# Tetris.net
KiCad netlist of a schematic drawn in Altium Designer
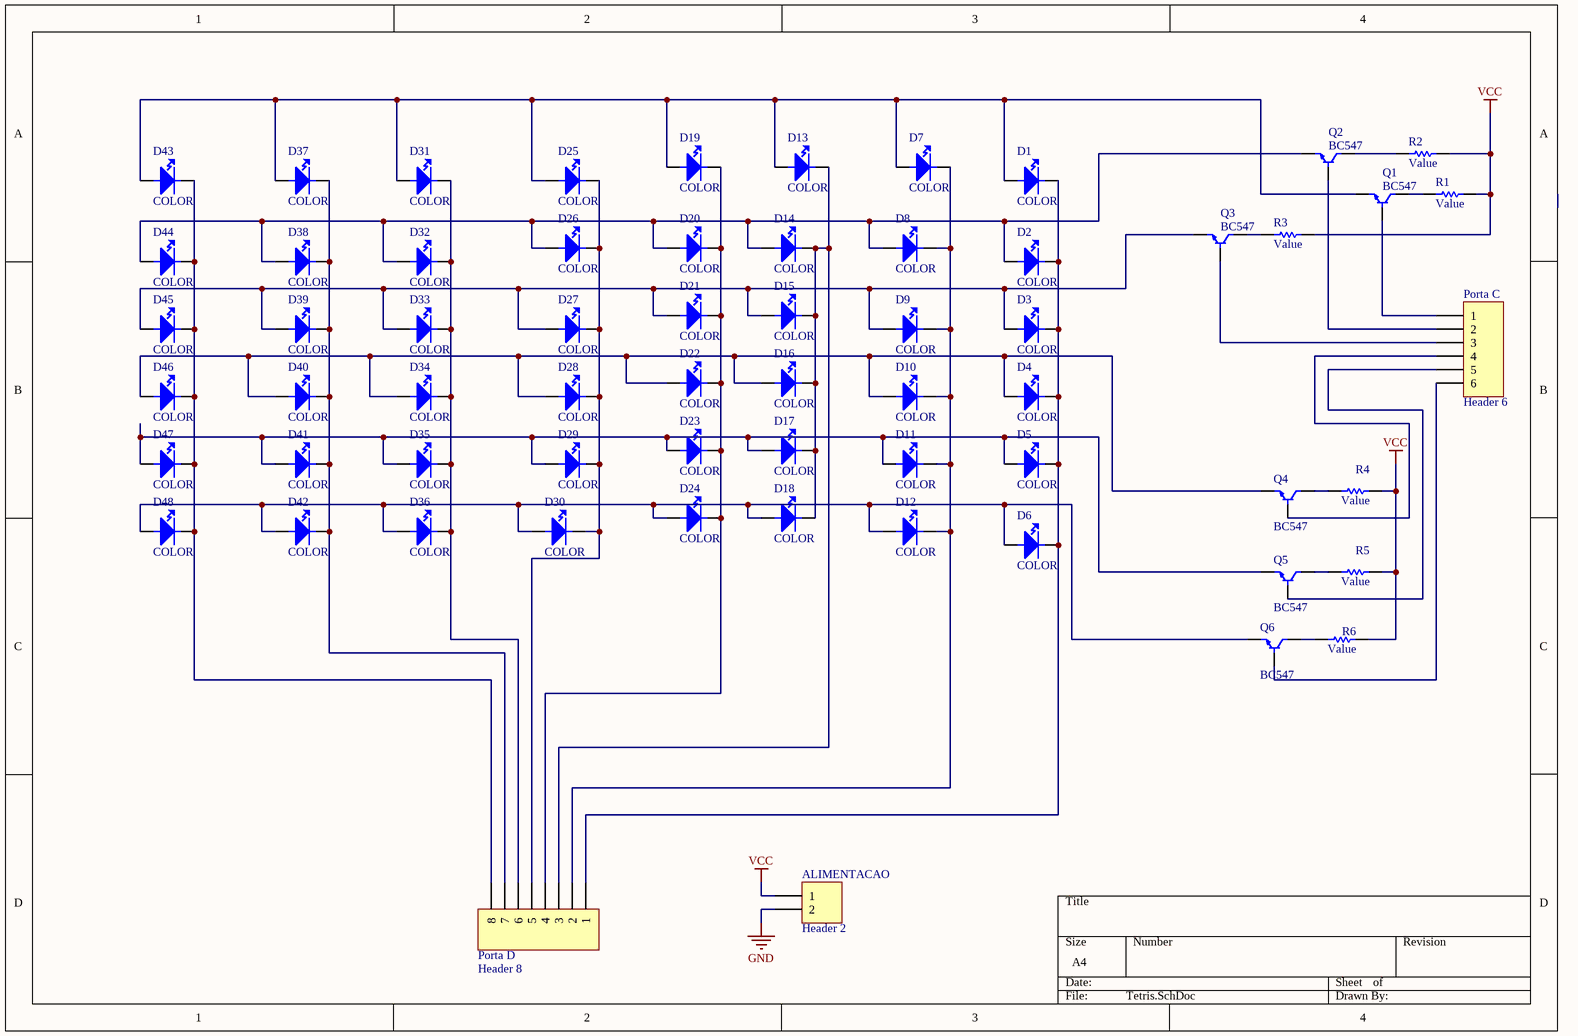
[diagram p0: Tetris.SchDoc]

(export (version "E")
  (design (tool "Eeschema 10.0.6"))
  (components
    (comp (ref "ALIMENTACAO")
      (value "Header 2")
      (footprint "HDR1X2")
      (description "Header, 2-Pin")
      (fields (field (name "PUBLISHER") "Altium Limited"))
      (libsource (lib "R2R - Nova") (part "Header 2"))
    )
    (comp (ref "D1")
      (value "COLOR")
      (footprint "TO1-5mm-Yellow")
      (description "Light Emitting Diode")
      (libsource (lib "R2R") (part "LED"))
    )
    (comp (ref "D2")
      (value "COLOR")
      (footprint "TO1-5mm-Yellow")
      (description "Light Emitting Diode")
      (libsource (lib "R2R") (part "LED"))
    )
    (comp (ref "D3")
      (value "COLOR")
      (footprint "TO1-5mm-Yellow")
      (description "Light Emitting Diode")
      (libsource (lib "R2R") (part "LED"))
    )
    (comp (ref "D4")
      (value "COLOR")
      (footprint "TO1-5mm-Yellow")
      (description "Light Emitting Diode")
      (libsource (lib "R2R") (part "LED"))
    )
    (comp (ref "D5")
      (value "COLOR")
      (footprint "TO1-5mm-Yellow")
      (description "Light Emitting Diode")
      (libsource (lib "R2R") (part "LED"))
    )
    (comp (ref "D6")
      (value "COLOR")
      (footprint "TO1-5mm-Yellow")
      (description "Light Emitting Diode")
      (libsource (lib "R2R") (part "LED"))
    )
    (comp (ref "D7")
      (value "COLOR")
      (footprint "TO1-5mm-Yellow")
      (description "Light Emitting Diode")
      (libsource (lib "R2R") (part "LED"))
    )
    (comp (ref "D8")
      (value "COLOR")
      (footprint "TO1-5mm-Yellow")
      (description "Light Emitting Diode")
      (libsource (lib "R2R") (part "LED"))
    )
    (comp (ref "D9")
      (value "COLOR")
      (footprint "TO1-5mm-Yellow")
      (description "Light Emitting Diode")
      (libsource (lib "R2R") (part "LED"))
    )
    (comp (ref "D10")
      (value "COLOR")
      (footprint "TO1-5mm-Yellow")
      (description "Light Emitting Diode")
      (libsource (lib "R2R") (part "LED"))
    )
    (comp (ref "D11")
      (value "COLOR")
      (footprint "TO1-5mm-Yellow")
      (description "Light Emitting Diode")
      (libsource (lib "R2R") (part "LED"))
    )
    (comp (ref "D12")
      (value "COLOR")
      (footprint "TO1-5mm-Yellow")
      (description "Light Emitting Diode")
      (libsource (lib "R2R") (part "LED"))
    )
    (comp (ref "D13")
      (value "COLOR")
      (footprint "TO1-5mm-Yellow")
      (description "Light Emitting Diode")
      (libsource (lib "R2R") (part "LED"))
    )
    (comp (ref "D14")
      (value "COLOR")
      (footprint "TO1-5mm-Yellow")
      (description "Light Emitting Diode")
      (libsource (lib "R2R") (part "LED"))
    )
    (comp (ref "D15")
      (value "COLOR")
      (footprint "TO1-5mm-Yellow")
      (description "Light Emitting Diode")
      (libsource (lib "R2R") (part "LED"))
    )
    (comp (ref "D16")
      (value "COLOR")
      (footprint "TO1-5mm-Yellow")
      (description "Light Emitting Diode")
      (libsource (lib "R2R") (part "LED"))
    )
    (comp (ref "D17")
      (value "COLOR")
      (footprint "TO1-5mm-Yellow")
      (description "Light Emitting Diode")
      (libsource (lib "R2R") (part "LED"))
    )
    (comp (ref "D18")
      (value "COLOR")
      (footprint "TO1-5mm-Yellow")
      (description "Light Emitting Diode")
      (libsource (lib "R2R") (part "LED"))
    )
    (comp (ref "D19")
      (value "COLOR")
      (footprint "TO1-5mm-Yellow")
      (description "Light Emitting Diode")
      (libsource (lib "R2R") (part "LED"))
    )
    (comp (ref "D20")
      (value "COLOR")
      (footprint "TO1-5mm-Yellow")
      (description "Light Emitting Diode")
      (libsource (lib "R2R") (part "LED"))
    )
    (comp (ref "D21")
      (value "COLOR")
      (footprint "TO1-5mm-Yellow")
      (description "Light Emitting Diode")
      (libsource (lib "R2R") (part "LED"))
    )
    (comp (ref "D22")
      (value "COLOR")
      (footprint "TO1-5mm-Yellow")
      (description "Light Emitting Diode")
      (libsource (lib "R2R") (part "LED"))
    )
    (comp (ref "D23")
      (value "COLOR")
      (footprint "TO1-5mm-Yellow")
      (description "Light Emitting Diode")
      (libsource (lib "R2R") (part "LED"))
    )
    (comp (ref "D24")
      (value "COLOR")
      (footprint "TO1-5mm-Yellow")
      (description "Light Emitting Diode")
      (libsource (lib "R2R") (part "LED"))
    )
    (comp (ref "D25")
      (value "COLOR")
      (footprint "TO1-5mm-Yellow")
      (description "Light Emitting Diode")
      (libsource (lib "R2R") (part "LED"))
    )
    (comp (ref "D26")
      (value "COLOR")
      (footprint "TO1-5mm-Yellow")
      (description "Light Emitting Diode")
      (libsource (lib "R2R") (part "LED"))
    )
    (comp (ref "D27")
      (value "COLOR")
      (footprint "TO1-5mm-Yellow")
      (description "Light Emitting Diode")
      (libsource (lib "R2R") (part "LED"))
    )
    (comp (ref "D28")
      (value "COLOR")
      (footprint "TO1-5mm-Yellow")
      (description "Light Emitting Diode")
      (libsource (lib "R2R") (part "LED"))
    )
    (comp (ref "D29")
      (value "COLOR")
      (footprint "TO1-5mm-Yellow")
      (description "Light Emitting Diode")
      (libsource (lib "R2R") (part "LED"))
    )
    (comp (ref "D30")
      (value "COLOR")
      (footprint "TO1-5mm-Yellow")
      (description "Light Emitting Diode")
      (libsource (lib "R2R") (part "LED"))
    )
    (comp (ref "D31")
      (value "COLOR")
      (footprint "TO1-5mm-Yellow")
      (description "Light Emitting Diode")
      (libsource (lib "R2R") (part "LED"))
    )
    (comp (ref "D32")
      (value "COLOR")
      (footprint "TO1-5mm-Yellow")
      (description "Light Emitting Diode")
      (libsource (lib "R2R") (part "LED"))
    )
    (comp (ref "D33")
      (value "COLOR")
      (footprint "TO1-5mm-Yellow")
      (description "Light Emitting Diode")
      (libsource (lib "R2R") (part "LED"))
    )
    (comp (ref "D34")
      (value "COLOR")
      (footprint "TO1-5mm-Yellow")
      (description "Light Emitting Diode")
      (libsource (lib "R2R") (part "LED"))
    )
    (comp (ref "D35")
      (value "COLOR")
      (footprint "TO1-5mm-Yellow")
      (description "Light Emitting Diode")
      (libsource (lib "R2R") (part "LED"))
    )
    (comp (ref "D36")
      (value "COLOR")
      (footprint "TO1-5mm-Yellow")
      (description "Light Emitting Diode")
      (libsource (lib "R2R") (part "LED"))
    )
    (comp (ref "D37")
      (value "COLOR")
      (footprint "TO1-5mm-Yellow")
      (description "Light Emitting Diode")
      (libsource (lib "R2R") (part "LED"))
    )
    (comp (ref "D38")
      (value "COLOR")
      (footprint "TO1-5mm-Yellow")
      (description "Light Emitting Diode")
      (libsource (lib "R2R") (part "LED"))
    )
    (comp (ref "D39")
      (value "COLOR")
      (footprint "TO1-5mm-Yellow")
      (description "Light Emitting Diode")
      (libsource (lib "R2R") (part "LED"))
    )
    (comp (ref "D40")
      (value "COLOR")
      (footprint "TO1-5mm-Yellow")
      (description "Light Emitting Diode")
      (libsource (lib "R2R") (part "LED"))
    )
    (comp (ref "D41")
      (value "COLOR")
      (footprint "TO1-5mm-Yellow")
      (description "Light Emitting Diode")
      (libsource (lib "R2R") (part "LED"))
    )
    (comp (ref "D42")
      (value "COLOR")
      (footprint "TO1-5mm-Yellow")
      (description "Light Emitting Diode")
      (libsource (lib "R2R") (part "LED"))
    )
    (comp (ref "D43")
      (value "COLOR")
      (footprint "TO1-5mm-Yellow")
      (description "Light Emitting Diode")
      (libsource (lib "R2R") (part "LED"))
    )
    (comp (ref "D44")
      (value "COLOR")
      (footprint "TO1-5mm-Yellow")
      (description "Light Emitting Diode")
      (libsource (lib "R2R") (part "LED"))
    )
    (comp (ref "D45")
      (value "COLOR")
      (footprint "TO1-5mm-Yellow")
      (description "Light Emitting Diode")
      (libsource (lib "R2R") (part "LED"))
    )
    (comp (ref "D46")
      (value "COLOR")
      (footprint "TO1-5mm-Yellow")
      (description "Light Emitting Diode")
      (libsource (lib "R2R") (part "LED"))
    )
    (comp (ref "D47")
      (value "COLOR")
      (footprint "TO1-5mm-Yellow")
      (description "Light Emitting Diode")
      (libsource (lib "R2R") (part "LED"))
    )
    (comp (ref "D48")
      (value "COLOR")
      (footprint "TO1-5mm-Yellow")
      (description "Light Emitting Diode")
      (libsource (lib "R2R") (part "LED"))
    )
    (comp (ref "Porta C")
      (value "Header 6")
      (footprint "HDR1X6")
      (description "Header, 6-Pin")
      (fields (field (name "PUBLISHER") "Altium Limited"))
      (libsource (lib "R2R - Nova") (part "Header 6"))
    )
    (comp (ref "Porta D")
      (value "Header 8")
      (footprint "HDR1X8")
      (description "Header, 8-Pin")
      (fields (field (name "PUBLISHER") "Altium Limited"))
      (libsource (lib "R2R - Nova") (part "Header 8"))
    )
    (comp (ref "Q1")
      (value "BC547")
      (footprint "TO-92/CBE")
      (description "NPN Epitaxial Silicon Transistor")
      (fields (field (name "COMPLEMENTARY PART") "BC557"))
      (libsource (lib "GPDSE") (part "BC547"))
    )
    (comp (ref "Q2")
      (value "BC547")
      (footprint "TO-92/CBE")
      (description "NPN Epitaxial Silicon Transistor")
      (fields (field (name "COMPLEMENTARY PART") "BC557"))
      (libsource (lib "GPDSE") (part "BC547"))
    )
    (comp (ref "Q3")
      (value "BC547")
      (footprint "TO-92/CBE")
      (description "NPN Epitaxial Silicon Transistor")
      (fields (field (name "COMPLEMENTARY PART") "BC557"))
      (libsource (lib "GPDSE") (part "BC547"))
    )
    (comp (ref "Q4")
      (value "BC547")
      (footprint "TO-92/CBE")
      (description "NPN Epitaxial Silicon Transistor")
      (fields (field (name "COMPLEMENTARY PART") "BC557"))
      (libsource (lib "GPDSE") (part "BC547"))
    )
    (comp (ref "Q5")
      (value "BC547")
      (footprint "TO-92/CBE")
      (description "NPN Epitaxial Silicon Transistor")
      (fields (field (name "COMPLEMENTARY PART") "BC557"))
      (libsource (lib "GPDSE") (part "BC547"))
    )
    (comp (ref "Q6")
      (value "BC547")
      (footprint "TO-92/CBE")
      (description "NPN Epitaxial Silicon Transistor")
      (fields (field (name "COMPLEMENTARY PART") "BC557"))
      (libsource (lib "GPDSE") (part "BC547"))
    )
    (comp (ref "R1")
      (value "Value")
      (footprint "R400-2.0mm")
      (description "Resistor")
      (fields (field (name "TOLERANCE") "5%") (field (name "PUBLISHER") "Altium Limited"))
      (libsource (lib "GPDSE") (part "Resistor"))
    )
    (comp (ref "R2")
      (value "Value")
      (footprint "R400-2.0mm")
      (description "Resistor")
      (fields (field (name "TOLERANCE") "5%") (field (name "PUBLISHER") "Altium Limited"))
      (libsource (lib "GPDSE") (part "Resistor"))
    )
    (comp (ref "R3")
      (value "Value")
      (footprint "R400-2.0mm")
      (description "Resistor")
      (fields (field (name "TOLERANCE") "5%") (field (name "PUBLISHER") "Altium Limited"))
      (libsource (lib "GPDSE") (part "Resistor"))
    )
    (comp (ref "R4")
      (value "Value")
      (footprint "R400-2.0mm")
      (description "Resistor")
      (fields (field (name "TOLERANCE") "5%") (field (name "PUBLISHER") "Altium Limited"))
      (libsource (lib "GPDSE") (part "Resistor"))
    )
    (comp (ref "R5")
      (value "Value")
      (footprint "R400-2.0mm")
      (description "Resistor")
      (fields (field (name "TOLERANCE") "5%") (field (name "PUBLISHER") "Altium Limited"))
      (libsource (lib "GPDSE") (part "Resistor"))
    )
    (comp (ref "R6")
      (value "Value")
      (footprint "R400-2.0mm")
      (description "Resistor")
      (fields (field (name "TOLERANCE") "5%") (field (name "PUBLISHER") "Altium Limited"))
      (libsource (lib "GPDSE") (part "Resistor"))
    )
  )
  (nets
    (net (code "1") (name "GND") (class "Default")
      (node (ref "ALIMENTACAO") (pin "2") (pinfunction "2_2") (pintype "passive"))
    )
    (net (code "2") (name "Net-(D1-PadA)") (class "Default")
      (node (ref "D1") (pin "A") (pinfunction "A_A") (pintype "passive"))
      (node (ref "D13") (pin "A") (pinfunction "A_A") (pintype "passive"))
      (node (ref "D19") (pin "A") (pinfunction "A_A") (pintype "passive"))
      (node (ref "D25") (pin "A") (pinfunction "A_A") (pintype "passive"))
      (node (ref "D31") (pin "A") (pinfunction "A_A") (pintype "passive"))
      (node (ref "D37") (pin "A") (pinfunction "A_A") (pintype "passive"))
      (node (ref "D43") (pin "A") (pinfunction "A_A") (pintype "passive"))
      (node (ref "D7") (pin "A") (pinfunction "A_A") (pintype "passive"))
      (node (ref "Q1") (pin "E") (pinfunction "E_E") (pintype "passive"))
    )
    (net (code "3") (name "Net-(D1-PadK)") (class "Default")
      (node (ref "D1") (pin "K") (pinfunction "K_K") (pintype "passive"))
      (node (ref "D2") (pin "K") (pinfunction "K_K") (pintype "passive"))
      (node (ref "D3") (pin "K") (pinfunction "K_K") (pintype "passive"))
      (node (ref "D4") (pin "K") (pinfunction "K_K") (pintype "passive"))
      (node (ref "D5") (pin "K") (pinfunction "K_K") (pintype "passive"))
      (node (ref "D6") (pin "K") (pinfunction "K_K") (pintype "passive"))
      (node (ref "Porta D") (pin "1") (pinfunction "1_1") (pintype "passive"))
    )
    (net (code "4") (name "Net-(D10-PadA)") (class "Default")
      (node (ref "D10") (pin "A") (pinfunction "A_A") (pintype "passive"))
      (node (ref "D16") (pin "A") (pinfunction "A_A") (pintype "passive"))
      (node (ref "D22") (pin "A") (pinfunction "A_A") (pintype "passive"))
      (node (ref "D28") (pin "A") (pinfunction "A_A") (pintype "passive"))
      (node (ref "D34") (pin "A") (pinfunction "A_A") (pintype "passive"))
      (node (ref "D4") (pin "A") (pinfunction "A_A") (pintype "passive"))
      (node (ref "D40") (pin "A") (pinfunction "A_A") (pintype "passive"))
      (node (ref "D46") (pin "A") (pinfunction "A_A") (pintype "passive"))
      (node (ref "Q4") (pin "E") (pinfunction "E_E") (pintype "passive"))
    )
    (net (code "5") (name "Net-(D10-PadK)") (class "Default")
      (node (ref "D10") (pin "K") (pinfunction "K_K") (pintype "passive"))
      (node (ref "D11") (pin "K") (pinfunction "K_K") (pintype "passive"))
      (node (ref "D12") (pin "K") (pinfunction "K_K") (pintype "passive"))
      (node (ref "D7") (pin "K") (pinfunction "K_K") (pintype "passive"))
      (node (ref "D8") (pin "K") (pinfunction "K_K") (pintype "passive"))
      (node (ref "D9") (pin "K") (pinfunction "K_K") (pintype "passive"))
      (node (ref "Porta D") (pin "2") (pinfunction "2_2") (pintype "passive"))
    )
    (net (code "6") (name "Net-(D11-PadA)") (class "Default")
      (node (ref "D11") (pin "A") (pinfunction "A_A") (pintype "passive"))
      (node (ref "D17") (pin "A") (pinfunction "A_A") (pintype "passive"))
      (node (ref "D23") (pin "A") (pinfunction "A_A") (pintype "passive"))
      (node (ref "D29") (pin "A") (pinfunction "A_A") (pintype "passive"))
      (node (ref "D35") (pin "A") (pinfunction "A_A") (pintype "passive"))
      (node (ref "D41") (pin "A") (pinfunction "A_A") (pintype "passive"))
      (node (ref "D47") (pin "A") (pinfunction "A_A") (pintype "passive"))
      (node (ref "D5") (pin "A") (pinfunction "A_A") (pintype "passive"))
      (node (ref "Q5") (pin "E") (pinfunction "E_E") (pintype "passive"))
    )
    (net (code "7") (name "Net-(D12-PadA)") (class "Default")
      (node (ref "D12") (pin "A") (pinfunction "A_A") (pintype "passive"))
      (node (ref "D18") (pin "A") (pinfunction "A_A") (pintype "passive"))
      (node (ref "D24") (pin "A") (pinfunction "A_A") (pintype "passive"))
      (node (ref "D30") (pin "A") (pinfunction "A_A") (pintype "passive"))
      (node (ref "D36") (pin "A") (pinfunction "A_A") (pintype "passive"))
      (node (ref "D42") (pin "A") (pinfunction "A_A") (pintype "passive"))
      (node (ref "D48") (pin "A") (pinfunction "A_A") (pintype "passive"))
      (node (ref "D6") (pin "A") (pinfunction "A_A") (pintype "passive"))
      (node (ref "Q6") (pin "E") (pinfunction "E_E") (pintype "passive"))
    )
    (net (code "8") (name "Net-(D13-PadK)") (class "Default")
      (node (ref "D13") (pin "K") (pinfunction "K_K") (pintype "passive"))
      (node (ref "D14") (pin "K") (pinfunction "K_K") (pintype "passive"))
      (node (ref "D15") (pin "K") (pinfunction "K_K") (pintype "passive"))
      (node (ref "D16") (pin "K") (pinfunction "K_K") (pintype "passive"))
      (node (ref "D17") (pin "K") (pinfunction "K_K") (pintype "passive"))
      (node (ref "D18") (pin "K") (pinfunction "K_K") (pintype "passive"))
      (node (ref "Porta D") (pin "3") (pinfunction "3_3") (pintype "passive"))
    )
    (net (code "9") (name "Net-(D14-PadA)") (class "Default")
      (node (ref "D14") (pin "A") (pinfunction "A_A") (pintype "passive"))
      (node (ref "D2") (pin "A") (pinfunction "A_A") (pintype "passive"))
      (node (ref "D20") (pin "A") (pinfunction "A_A") (pintype "passive"))
      (node (ref "D26") (pin "A") (pinfunction "A_A") (pintype "passive"))
      (node (ref "D32") (pin "A") (pinfunction "A_A") (pintype "passive"))
      (node (ref "D38") (pin "A") (pinfunction "A_A") (pintype "passive"))
      (node (ref "D44") (pin "A") (pinfunction "A_A") (pintype "passive"))
      (node (ref "D8") (pin "A") (pinfunction "A_A") (pintype "passive"))
      (node (ref "Q2") (pin "E") (pinfunction "E_E") (pintype "passive"))
    )
    (net (code "10") (name "Net-(D15-PadA)") (class "Default")
      (node (ref "D15") (pin "A") (pinfunction "A_A") (pintype "passive"))
      (node (ref "D21") (pin "A") (pinfunction "A_A") (pintype "passive"))
      (node (ref "D27") (pin "A") (pinfunction "A_A") (pintype "passive"))
      (node (ref "D3") (pin "A") (pinfunction "A_A") (pintype "passive"))
      (node (ref "D33") (pin "A") (pinfunction "A_A") (pintype "passive"))
      (node (ref "D39") (pin "A") (pinfunction "A_A") (pintype "passive"))
      (node (ref "D45") (pin "A") (pinfunction "A_A") (pintype "passive"))
      (node (ref "D9") (pin "A") (pinfunction "A_A") (pintype "passive"))
      (node (ref "Q3") (pin "E") (pinfunction "E_E") (pintype "passive"))
    )
    (net (code "11") (name "Net-(D19-PadK)") (class "Default")
      (node (ref "D19") (pin "K") (pinfunction "K_K") (pintype "passive"))
      (node (ref "D20") (pin "K") (pinfunction "K_K") (pintype "passive"))
      (node (ref "D21") (pin "K") (pinfunction "K_K") (pintype "passive"))
      (node (ref "D22") (pin "K") (pinfunction "K_K") (pintype "passive"))
      (node (ref "D23") (pin "K") (pinfunction "K_K") (pintype "passive"))
      (node (ref "D24") (pin "K") (pinfunction "K_K") (pintype "passive"))
      (node (ref "Porta D") (pin "4") (pinfunction "4_4") (pintype "passive"))
    )
    (net (code "12") (name "Net-(D25-PadK)") (class "Default")
      (node (ref "D25") (pin "K") (pinfunction "K_K") (pintype "passive"))
      (node (ref "D26") (pin "K") (pinfunction "K_K") (pintype "passive"))
      (node (ref "D27") (pin "K") (pinfunction "K_K") (pintype "passive"))
      (node (ref "D28") (pin "K") (pinfunction "K_K") (pintype "passive"))
      (node (ref "D29") (pin "K") (pinfunction "K_K") (pintype "passive"))
      (node (ref "D30") (pin "K") (pinfunction "K_K") (pintype "passive"))
      (node (ref "Porta D") (pin "5") (pinfunction "5_5") (pintype "passive"))
    )
    (net (code "13") (name "Net-(D31-PadK)") (class "Default")
      (node (ref "D31") (pin "K") (pinfunction "K_K") (pintype "passive"))
      (node (ref "D32") (pin "K") (pinfunction "K_K") (pintype "passive"))
      (node (ref "D33") (pin "K") (pinfunction "K_K") (pintype "passive"))
      (node (ref "D34") (pin "K") (pinfunction "K_K") (pintype "passive"))
      (node (ref "D35") (pin "K") (pinfunction "K_K") (pintype "passive"))
      (node (ref "D36") (pin "K") (pinfunction "K_K") (pintype "passive"))
      (node (ref "Porta D") (pin "6") (pinfunction "6_6") (pintype "passive"))
    )
    (net (code "14") (name "Net-(D37-PadK)") (class "Default")
      (node (ref "D37") (pin "K") (pinfunction "K_K") (pintype "passive"))
      (node (ref "D38") (pin "K") (pinfunction "K_K") (pintype "passive"))
      (node (ref "D39") (pin "K") (pinfunction "K_K") (pintype "passive"))
      (node (ref "D40") (pin "K") (pinfunction "K_K") (pintype "passive"))
      (node (ref "D41") (pin "K") (pinfunction "K_K") (pintype "passive"))
      (node (ref "D42") (pin "K") (pinfunction "K_K") (pintype "passive"))
      (node (ref "Porta D") (pin "7") (pinfunction "7_7") (pintype "passive"))
    )
    (net (code "15") (name "Net-(D43-PadK)") (class "Default")
      (node (ref "D43") (pin "K") (pinfunction "K_K") (pintype "passive"))
      (node (ref "D44") (pin "K") (pinfunction "K_K") (pintype "passive"))
      (node (ref "D45") (pin "K") (pinfunction "K_K") (pintype "passive"))
      (node (ref "D46") (pin "K") (pinfunction "K_K") (pintype "passive"))
      (node (ref "D47") (pin "K") (pinfunction "K_K") (pintype "passive"))
      (node (ref "D48") (pin "K") (pinfunction "K_K") (pintype "passive"))
      (node (ref "Porta D") (pin "8") (pinfunction "8_8") (pintype "passive"))
    )
    (net (code "16") (name "Net-(Porta C-Pad1)") (class "Default")
      (node (ref "Porta C") (pin "1") (pinfunction "1_1") (pintype "passive"))
      (node (ref "Q1") (pin "B") (pinfunction "B_B") (pintype "passive"))
    )
    (net (code "17") (name "Net-(Porta C-Pad2)") (class "Default")
      (node (ref "Porta C") (pin "2") (pinfunction "2_2") (pintype "passive"))
      (node (ref "Q2") (pin "B") (pinfunction "B_B") (pintype "passive"))
    )
    (net (code "18") (name "Net-(Porta C-Pad3)") (class "Default")
      (node (ref "Porta C") (pin "3") (pinfunction "3_3") (pintype "passive"))
      (node (ref "Q3") (pin "B") (pinfunction "B_B") (pintype "passive"))
    )
    (net (code "19") (name "Net-(Porta C-Pad4)") (class "Default")
      (node (ref "Porta C") (pin "4") (pinfunction "4_4") (pintype "passive"))
      (node (ref "Q4") (pin "B") (pinfunction "B_B") (pintype "passive"))
    )
    (net (code "20") (name "Net-(Porta C-Pad5)") (class "Default")
      (node (ref "Porta C") (pin "5") (pinfunction "5_5") (pintype "passive"))
      (node (ref "Q5") (pin "B") (pinfunction "B_B") (pintype "passive"))
    )
    (net (code "21") (name "Net-(Porta C-Pad6)") (class "Default")
      (node (ref "Porta C") (pin "6") (pinfunction "6_6") (pintype "passive"))
      (node (ref "Q6") (pin "B") (pinfunction "B_B") (pintype "passive"))
    )
    (net (code "22") (name "Net-(Q1-PadC)") (class "Default")
      (node (ref "Q1") (pin "C") (pinfunction "C_C") (pintype "passive"))
      (node (ref "R1") (pin "1") (pinfunction "1_1") (pintype "passive"))
    )
    (net (code "23") (name "Net-(Q2-PadC)") (class "Default")
      (node (ref "Q2") (pin "C") (pinfunction "C_C") (pintype "passive"))
      (node (ref "R2") (pin "1") (pinfunction "1_1") (pintype "passive"))
    )
    (net (code "24") (name "Net-(Q3-PadC)") (class "Default")
      (node (ref "Q3") (pin "C") (pinfunction "C_C") (pintype "passive"))
      (node (ref "R3") (pin "1") (pinfunction "1_1") (pintype "passive"))
    )
    (net (code "25") (name "Net-(Q4-PadC)") (class "Default")
      (node (ref "Q4") (pin "C") (pinfunction "C_C") (pintype "passive"))
      (node (ref "R4") (pin "1") (pinfunction "1_1") (pintype "passive"))
    )
    (net (code "26") (name "Net-(Q5-PadC)") (class "Default")
      (node (ref "Q5") (pin "C") (pinfunction "C_C") (pintype "passive"))
      (node (ref "R5") (pin "1") (pinfunction "1_1") (pintype "passive"))
    )
    (net (code "27") (name "Net-(Q6-PadC)") (class "Default")
      (node (ref "Q6") (pin "C") (pinfunction "C_C") (pintype "passive"))
      (node (ref "R6") (pin "1") (pinfunction "1_1") (pintype "passive"))
    )
    (net (code "28") (name "VCC") (class "Default")
      (node (ref "ALIMENTACAO") (pin "1") (pinfunction "1_1") (pintype "passive"))
      (node (ref "R1") (pin "2") (pinfunction "2_2") (pintype "passive"))
      (node (ref "R2") (pin "2") (pinfunction "2_2") (pintype "passive"))
      (node (ref "R3") (pin "2") (pinfunction "2_2") (pintype "passive"))
      (node (ref "R4") (pin "2") (pinfunction "2_2") (pintype "passive"))
      (node (ref "R5") (pin "2") (pinfunction "2_2") (pintype "passive"))
      (node (ref "R6") (pin "2") (pinfunction "2_2") (pintype "passive"))
    )
  )
)
